# SparkFun_I2S_Audio_Breakout.net
KiCad netlist of a schematic drawn in EAGLE
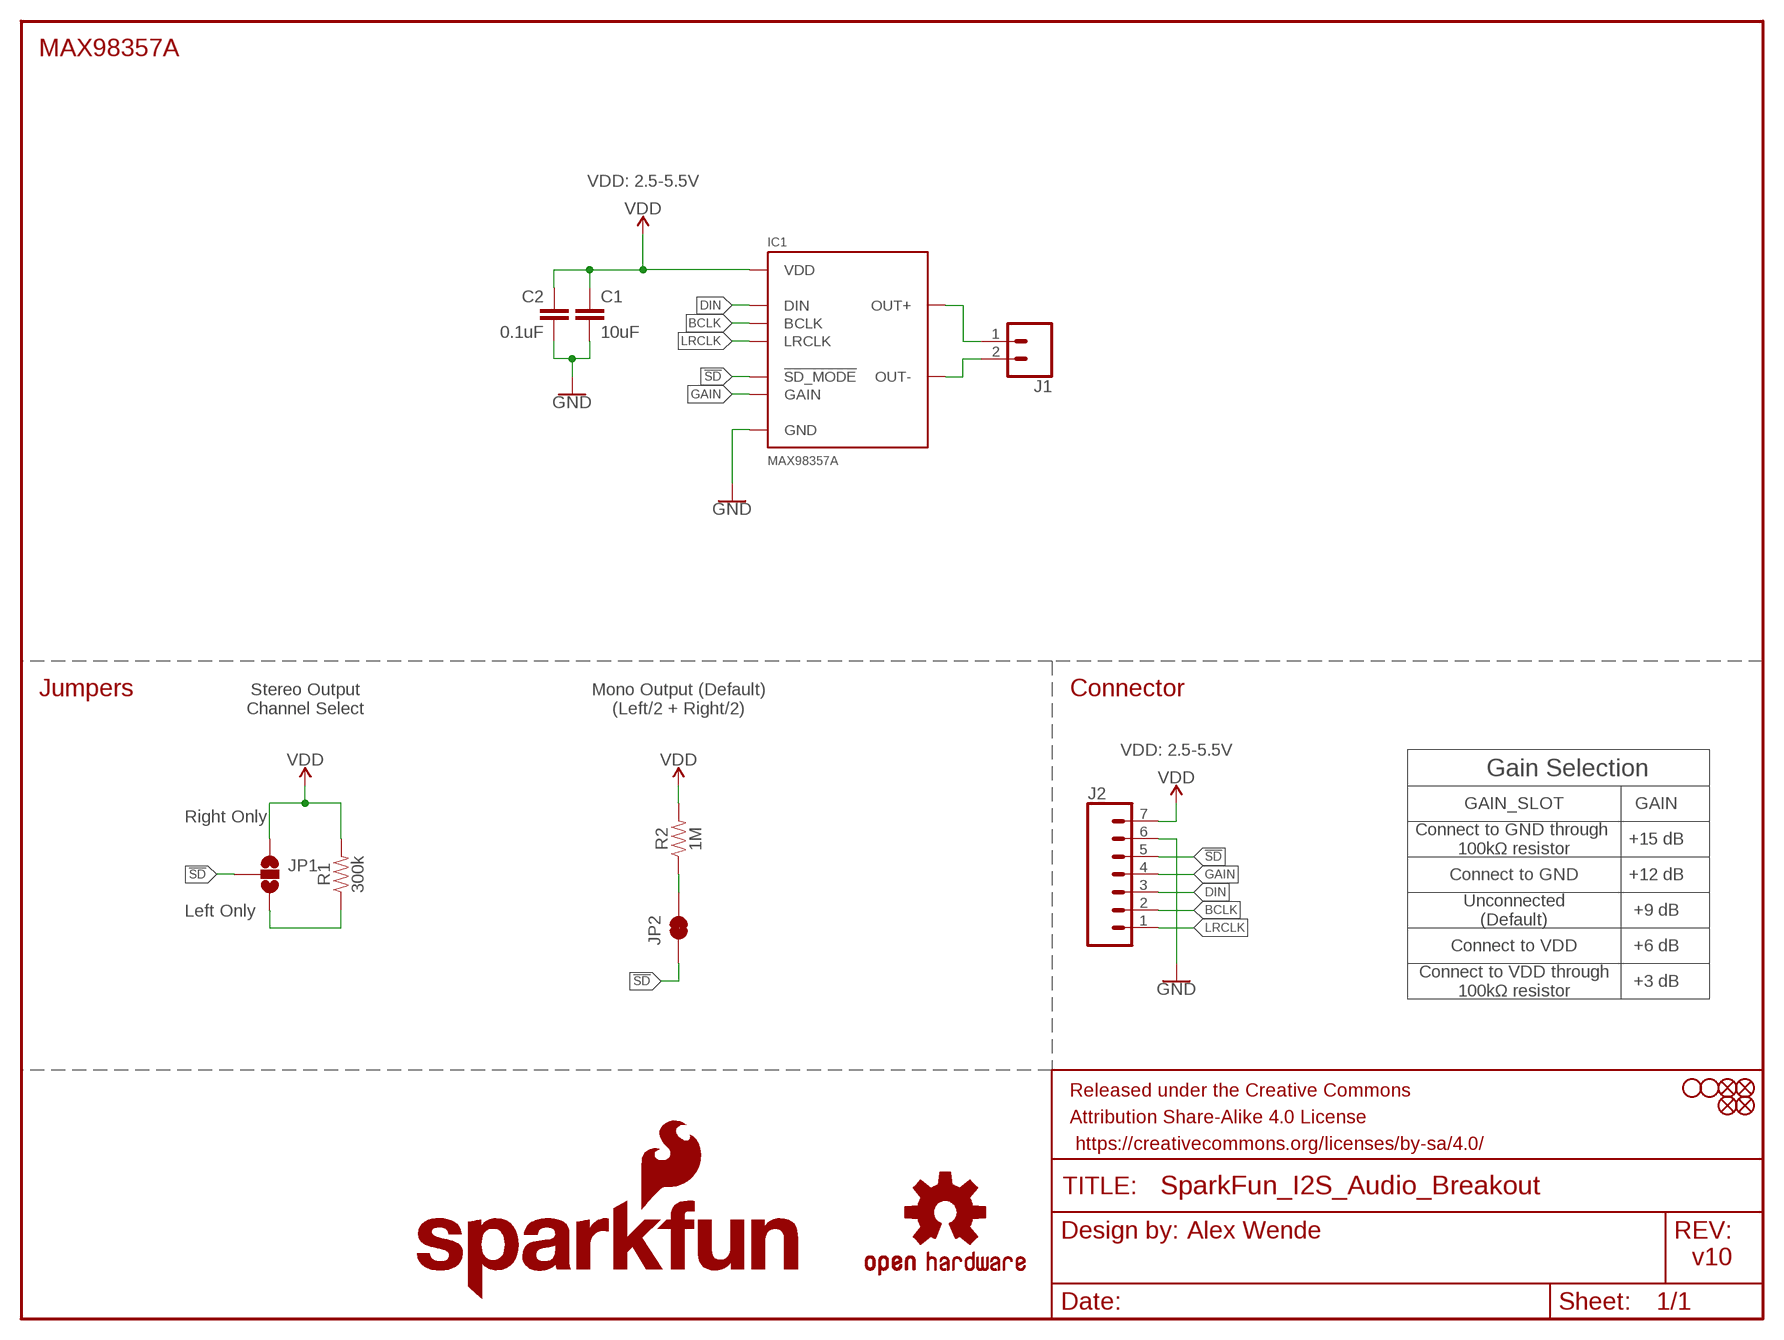
[diagram p0: schematic, sheet 1]

(export (version "E")
  (design (tool "Eeschema 10.0.6"))
  (components
    (comp (ref "C1")
      (value "10uF")
      (footprint "eagle-import:0805")
      (libsource (lib "eagle-import") (part "10UF-0805-10V-10%"))
    )
    (comp (ref "C2")
      (value "0.1uF")
      (footprint "eagle-import:0603")
      (libsource (lib "eagle-import") (part "0.1UF-0603-25V-(+80/-20%)"))
    )
    (comp (ref "FD1")
      (value "FIDUCIALUFIDUCIAL")
      (footprint "eagle-import:FIDUCIAL-MICRO")
      (libsource (lib "eagle-import") (part "FIDUCIALUFIDUCIAL"))
    )
    (comp (ref "FD2")
      (value "FIDUCIALUFIDUCIAL")
      (footprint "eagle-import:FIDUCIAL-MICRO")
      (libsource (lib "eagle-import") (part "FIDUCIALUFIDUCIAL"))
    )
    (comp (ref "FD3")
      (value "FIDUCIALUFIDUCIAL")
      (footprint "eagle-import:FIDUCIAL-MICRO")
      (libsource (lib "eagle-import") (part "FIDUCIALUFIDUCIAL"))
    )
    (comp (ref "FD4")
      (value "FIDUCIALUFIDUCIAL")
      (footprint "eagle-import:FIDUCIAL-MICRO")
      (libsource (lib "eagle-import") (part "FIDUCIALUFIDUCIAL"))
    )
    (comp (ref "FRAME1")
      (value "FRAME-LETTER")
      (footprint "eagle-import:CREATIVE_COMMONS")
      (libsource (lib "eagle-import") (part "FRAME-LETTER"))
    )
    (comp (ref "H1")
      (value "STAND-OFF")
      (footprint "eagle-import:STAND-OFF")
      (libsource (lib "eagle-import") (part "STAND-OFF"))
    )
    (comp (ref "H2")
      (value "STAND-OFF")
      (footprint "eagle-import:STAND-OFF")
      (libsource (lib "eagle-import") (part "STAND-OFF"))
    )
    (comp (ref "IC1")
      (value "MAX98357A")
      (footprint "eagle-import:TQFN-16")
      (libsource (lib "eagle-import") (part "MAX98357A"))
    )
    (comp (ref "J1")
      (value "CONN_023.5MM-NO_SILK")
      (footprint "eagle-import:SCREWTERMINAL-3.5MM-2-NS")
      (libsource (lib "eagle-import") (part "CONN_023.5MM-NO_SILK"))
    )
    (comp (ref "J2")
      (value "CONN_07NO_SILK")
      (footprint "eagle-import:1X07_NO_SILK")
      (libsource (lib "eagle-import") (part "CONN_07NO_SILK"))
    )
    (comp (ref "JP1")
      (value "JUMPER-SMT_3_NO_NO-SILK")
      (footprint "eagle-import:SMT-JUMPER_3_NO_NO-SILK")
      (libsource (lib "eagle-import") (part "JUMPER-SMT_3_NO_NO-SILK"))
    )
    (comp (ref "JP2")
      (value "JUMPER-SMT_2_NC_TRACE_NO-SILK")
      (footprint "eagle-import:SMT-JUMPER_2_NC_TRACE_NO-SILK")
      (libsource (lib "eagle-import") (part "JUMPER-SMT_2_NC_TRACE_NO-SILK"))
    )
    (comp (ref "LOGO1")
      (value "SFE_LOGO_NAME_FLAME.1_INCH")
      (footprint "eagle-import:SFE_LOGO_NAME_FLAME_.1")
      (libsource (lib "eagle-import") (part "SFE_LOGO_NAME_FLAME.1_INCH"))
    )
    (comp (ref "LOGO2")
      (value "OSHW-LOGOS")
      (footprint "eagle-import:OSHW-LOGO-S")
      (libsource (lib "eagle-import") (part "OSHW-LOGOS"))
    )
    (comp (ref "R1")
      (value "300k")
      (footprint "eagle-import:0603")
      (libsource (lib "eagle-import") (part "300KOHM-0603-1/10W-1%"))
    )
    (comp (ref "R2")
      (value "1M")
      (footprint "eagle-import:0603")
      (libsource (lib "eagle-import") (part "1MOHM-0603-1/4W-5%"))
    )
  )
  (nets
    (net (code "1") (name "/~{SD}") (class "Default")
      (node (ref "IC1") (pin "P$4") (pinfunction "~{SD_MODE}_P$4") (pintype "bidirectional"))
      (node (ref "J2") (pin "5") (pinfunction "5_5") (pintype "passive"))
      (node (ref "JP1") (pin "2") (pinfunction "2_2") (pintype "passive"))
      (node (ref "JP2") (pin "1") (pinfunction "1_1") (pintype "passive"))
    )
    (net (code "2") (name "BCLK") (class "Default")
      (node (ref "IC1") (pin "P$16") (pinfunction "BCLK_P$16") (pintype "bidirectional"))
      (node (ref "J2") (pin "2") (pinfunction "2_2") (pintype "passive"))
    )
    (net (code "3") (name "DIN") (class "Default")
      (node (ref "IC1") (pin "P$1") (pinfunction "DIN_P$1") (pintype "bidirectional"))
      (node (ref "J2") (pin "3") (pinfunction "3_3") (pintype "passive"))
    )
    (net (code "4") (name "GAIN") (class "Default")
      (node (ref "IC1") (pin "P$2") (pinfunction "GAIN_P$2") (pintype "bidirectional"))
      (node (ref "J2") (pin "4") (pinfunction "4_4") (pintype "passive"))
    )
    (net (code "5") (name "GND") (class "Default")
      (node (ref "C1") (pin "2") (pinfunction "2_2") (pintype "passive"))
      (node (ref "C2") (pin "2") (pinfunction "2_2") (pintype "passive"))
      (node (ref "IC1") (pin "P$11") (pinfunction "GND_P$11") (pintype "bidirectional"))
      (node (ref "IC1") (pin "P$15") (pinfunction "GND_P$15") (pintype "bidirectional"))
      (node (ref "IC1") (pin "P$3") (pinfunction "GND_P$3") (pintype "bidirectional"))
      (node (ref "IC1") (pin "P$EP") (pinfunction "GND_P$EP") (pintype "bidirectional"))
      (node (ref "J2") (pin "6") (pinfunction "6_6") (pintype "passive"))
    )
    (net (code "6") (name "LRCLK") (class "Default")
      (node (ref "IC1") (pin "P$14") (pinfunction "LRCLK_P$14") (pintype "bidirectional"))
      (node (ref "J2") (pin "1") (pinfunction "1_1") (pintype "passive"))
    )
    (net (code "7") (name "Net-(IC1-OUT+)") (class "Default")
      (node (ref "IC1") (pin "P$9") (pinfunction "OUT+_P$9") (pintype "bidirectional"))
      (node (ref "J1") (pin "1") (pinfunction "1_1") (pintype "passive"))
    )
    (net (code "8") (name "Net-(IC1-OUT-)") (class "Default")
      (node (ref "IC1") (pin "P$10") (pinfunction "OUT-_P$10") (pintype "bidirectional"))
      (node (ref "J1") (pin "2") (pinfunction "2_2") (pintype "passive"))
    )
    (net (code "9") (name "Net-(JP1-Pad3)") (class "Default")
      (node (ref "JP1") (pin "3") (pinfunction "3_3") (pintype "passive"))
      (node (ref "R1") (pin "1") (pinfunction "1_1") (pintype "passive"))
    )
    (net (code "10") (name "Net-(JP2-Pad2)") (class "Default")
      (node (ref "JP2") (pin "2") (pinfunction "2_2") (pintype "passive"))
      (node (ref "R2") (pin "1") (pinfunction "1_1") (pintype "passive"))
    )
    (net (code "11") (name "VDD") (class "Default")
      (node (ref "C1") (pin "1") (pinfunction "1_1") (pintype "passive"))
      (node (ref "C2") (pin "1") (pinfunction "1_1") (pintype "passive"))
      (node (ref "IC1") (pin "P$7") (pinfunction "VDD_P$7") (pintype "bidirectional"))
      (node (ref "IC1") (pin "P$8") (pinfunction "VDD_P$8") (pintype "bidirectional"))
      (node (ref "J2") (pin "7") (pinfunction "7_7") (pintype "passive"))
      (node (ref "JP1") (pin "1") (pinfunction "1_1") (pintype "passive"))
      (node (ref "R1") (pin "2") (pinfunction "2_2") (pintype "passive"))
      (node (ref "R2") (pin "2") (pinfunction "2_2") (pintype "passive"))
    )
  )
)
